# EasyEDA_NeuroHab_CS_Module_Project.net
KiCad netlist of a schematic drawn in EasyEDA Pro
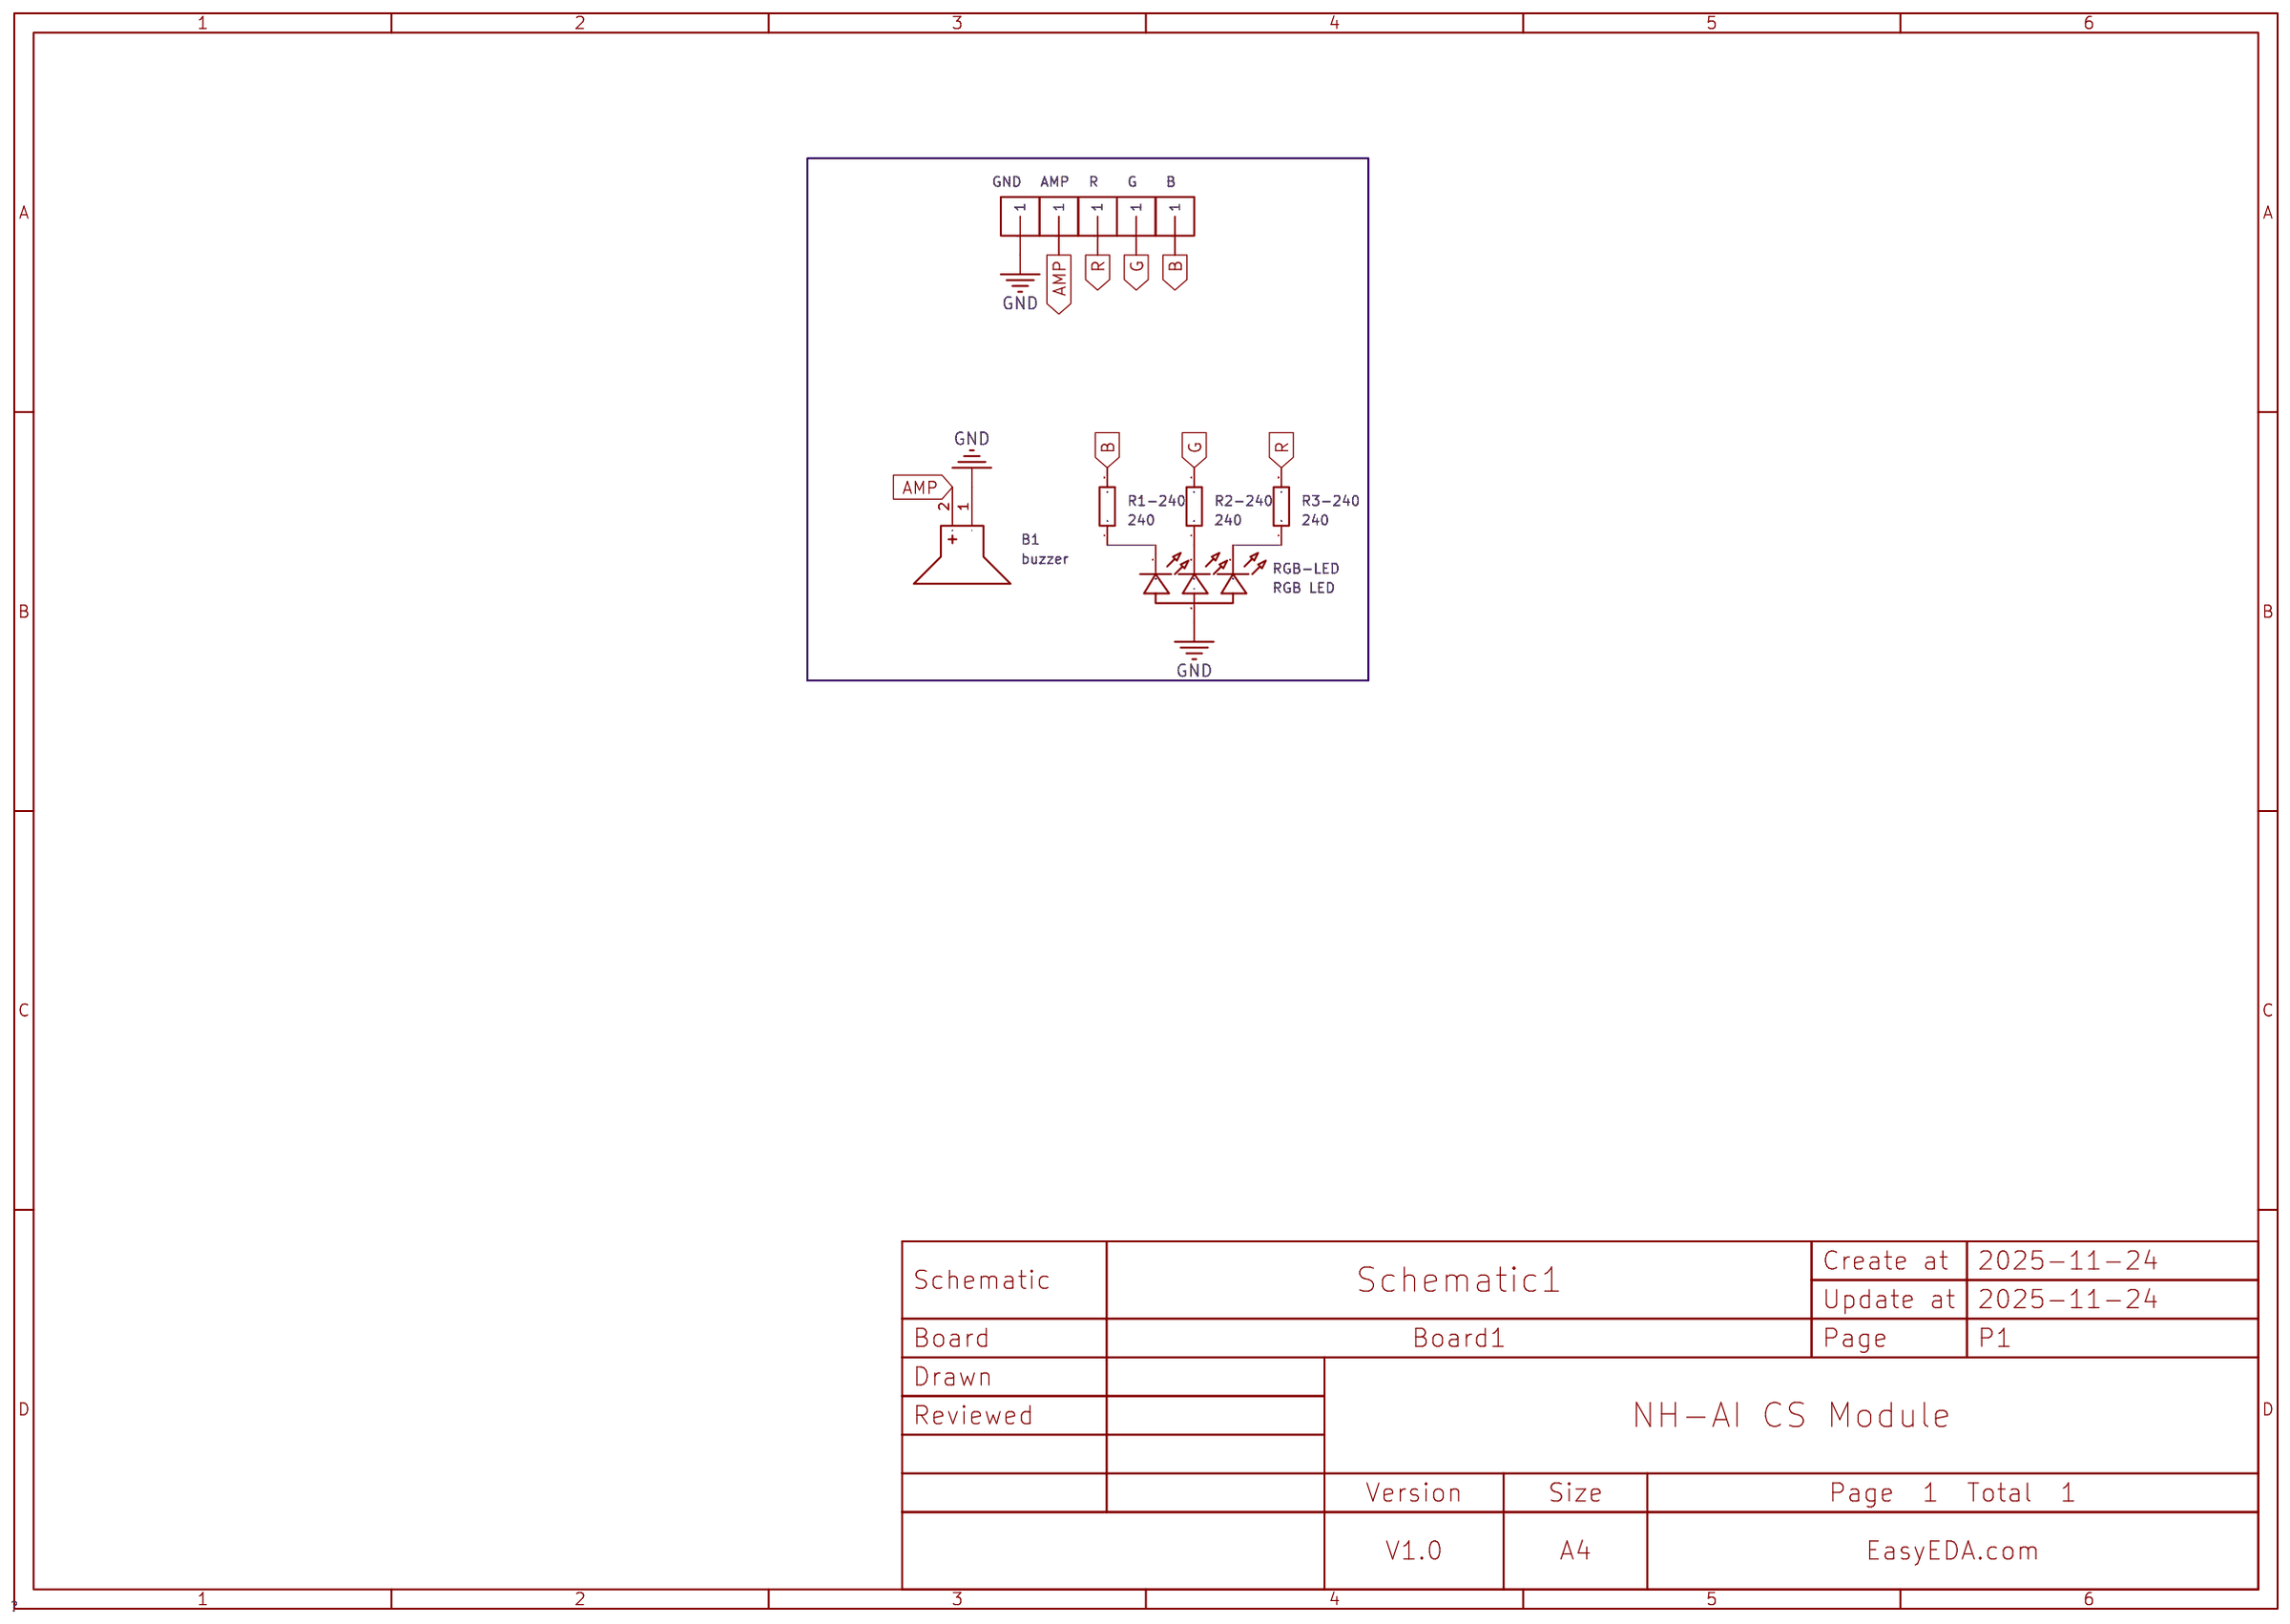
[diagram p0: schematic sheet]

(export (version "E")
  (design (tool "Eeschema 10.0.6"))
  (components
    (comp (ref "AMP")
      (value "~")
      (footprint "easyedapro:2.54mm Screw Terminal")
      (libsource (lib "easyedapro") (part "2.54mm Screw Terminal Block"))
    )
    (comp (ref "B")
      (value "~")
      (footprint "easyedapro:2.54mm Screw Terminal")
      (libsource (lib "easyedapro") (part "2.54mm Screw Terminal Block"))
    )
    (comp (ref "B1")
      (value "buzzer")
      (footprint "easyedapro:BUZ-TH_BD12.0-P6.00-D0.9-RD")
      (libsource (lib "easyedapro") (part "BUZZER"))
    )
    (comp (ref "G")
      (value "~")
      (footprint "easyedapro:2.54mm Screw Terminal")
      (libsource (lib "easyedapro") (part "2.54mm Screw Terminal Block"))
    )
    (comp (ref "GND")
      (value "~")
      (footprint "easyedapro:2.54mm Screw Terminal")
      (libsource (lib "easyedapro") (part "2.54mm Screw Terminal Block"))
    )
    (comp (ref "R")
      (value "~")
      (footprint "easyedapro:2.54mm Screw Terminal")
      (libsource (lib "easyedapro") (part "2.54mm Screw Terminal Block"))
    )
    (comp (ref "R1-240")
      (value "240")
      (footprint "easyedapro:R0603")
      (libsource (lib "easyedapro") (part "Res"))
    )
    (comp (ref "R2-240")
      (value "240")
      (footprint "easyedapro:R0603")
      (libsource (lib "easyedapro") (part "Res"))
    )
    (comp (ref "R3-240")
      (value "240")
      (footprint "easyedapro:R0603")
      (libsource (lib "easyedapro") (part "Res"))
    )
    (comp (ref "RGB-LED")
      (value "RGB LED")
      (footprint "easyedapro:LED-TH_4P-BD5.8-P1.25_SL-BUXG6B1294-A")
      (fields (field (name "Manufacturer Part") "SL-BUXG6B1294-A"))
      (libsource (lib "easyedapro") (part "SL-BUXG6B1294-A"))
    )
  )
  (nets
    (net (code "1") (name "AMP") (class "Default")
      (node (ref "AMP") (pin "1") (pinfunction "1_1") (pintype "input"))
      (node (ref "B1") (pin "2") (pinfunction "+_2") (pintype "unspecified"))
    )
    (net (code "2") (name "B") (class "Default")
      (node (ref "B") (pin "1") (pinfunction "1_1") (pintype "input"))
      (node (ref "R1-240") (pin "2") (pinfunction "2_2") (pintype "input"))
    )
    (net (code "3") (name "G") (class "Default")
      (node (ref "G") (pin "1") (pinfunction "1_1") (pintype "input"))
      (node (ref "R2-240") (pin "2") (pinfunction "2_2") (pintype "input"))
    )
    (net (code "4") (name "GND") (class "Default")
      (node (ref "B1") (pin "1") (pinfunction "-_1") (pintype "unspecified"))
      (node (ref "GND") (pin "1") (pinfunction "1_1") (pintype "input"))
      (node (ref "RGB-LED") (pin "2") (pinfunction "A_2") (pintype "unspecified"))
    )
    (net (code "5") (name "Net-(R1-240-Pad1)") (class "Default")
      (node (ref "R1-240") (pin "1") (pinfunction "1_1") (pintype "input"))
      (node (ref "RGB-LED") (pin "4") (pinfunction "C_4") (pintype "unspecified"))
    )
    (net (code "6") (name "Net-(R2-240-Pad1)") (class "Default")
      (node (ref "R2-240") (pin "1") (pinfunction "1_1") (pintype "input"))
      (node (ref "RGB-LED") (pin "3") (pinfunction "C_3") (pintype "unspecified"))
    )
    (net (code "7") (name "Net-(R3-240-Pad1)") (class "Default")
      (node (ref "R3-240") (pin "1") (pinfunction "1_1") (pintype "input"))
      (node (ref "RGB-LED") (pin "1") (pinfunction "C_1") (pintype "unspecified"))
    )
    (net (code "8") (name "R") (class "Default")
      (node (ref "R") (pin "1") (pinfunction "1_1") (pintype "input"))
      (node (ref "R3-240") (pin "2") (pinfunction "2_2") (pintype "input"))
    )
  )
)
